# Main_mouse.net
KiCad netlist of a schematic drawn in EAGLE
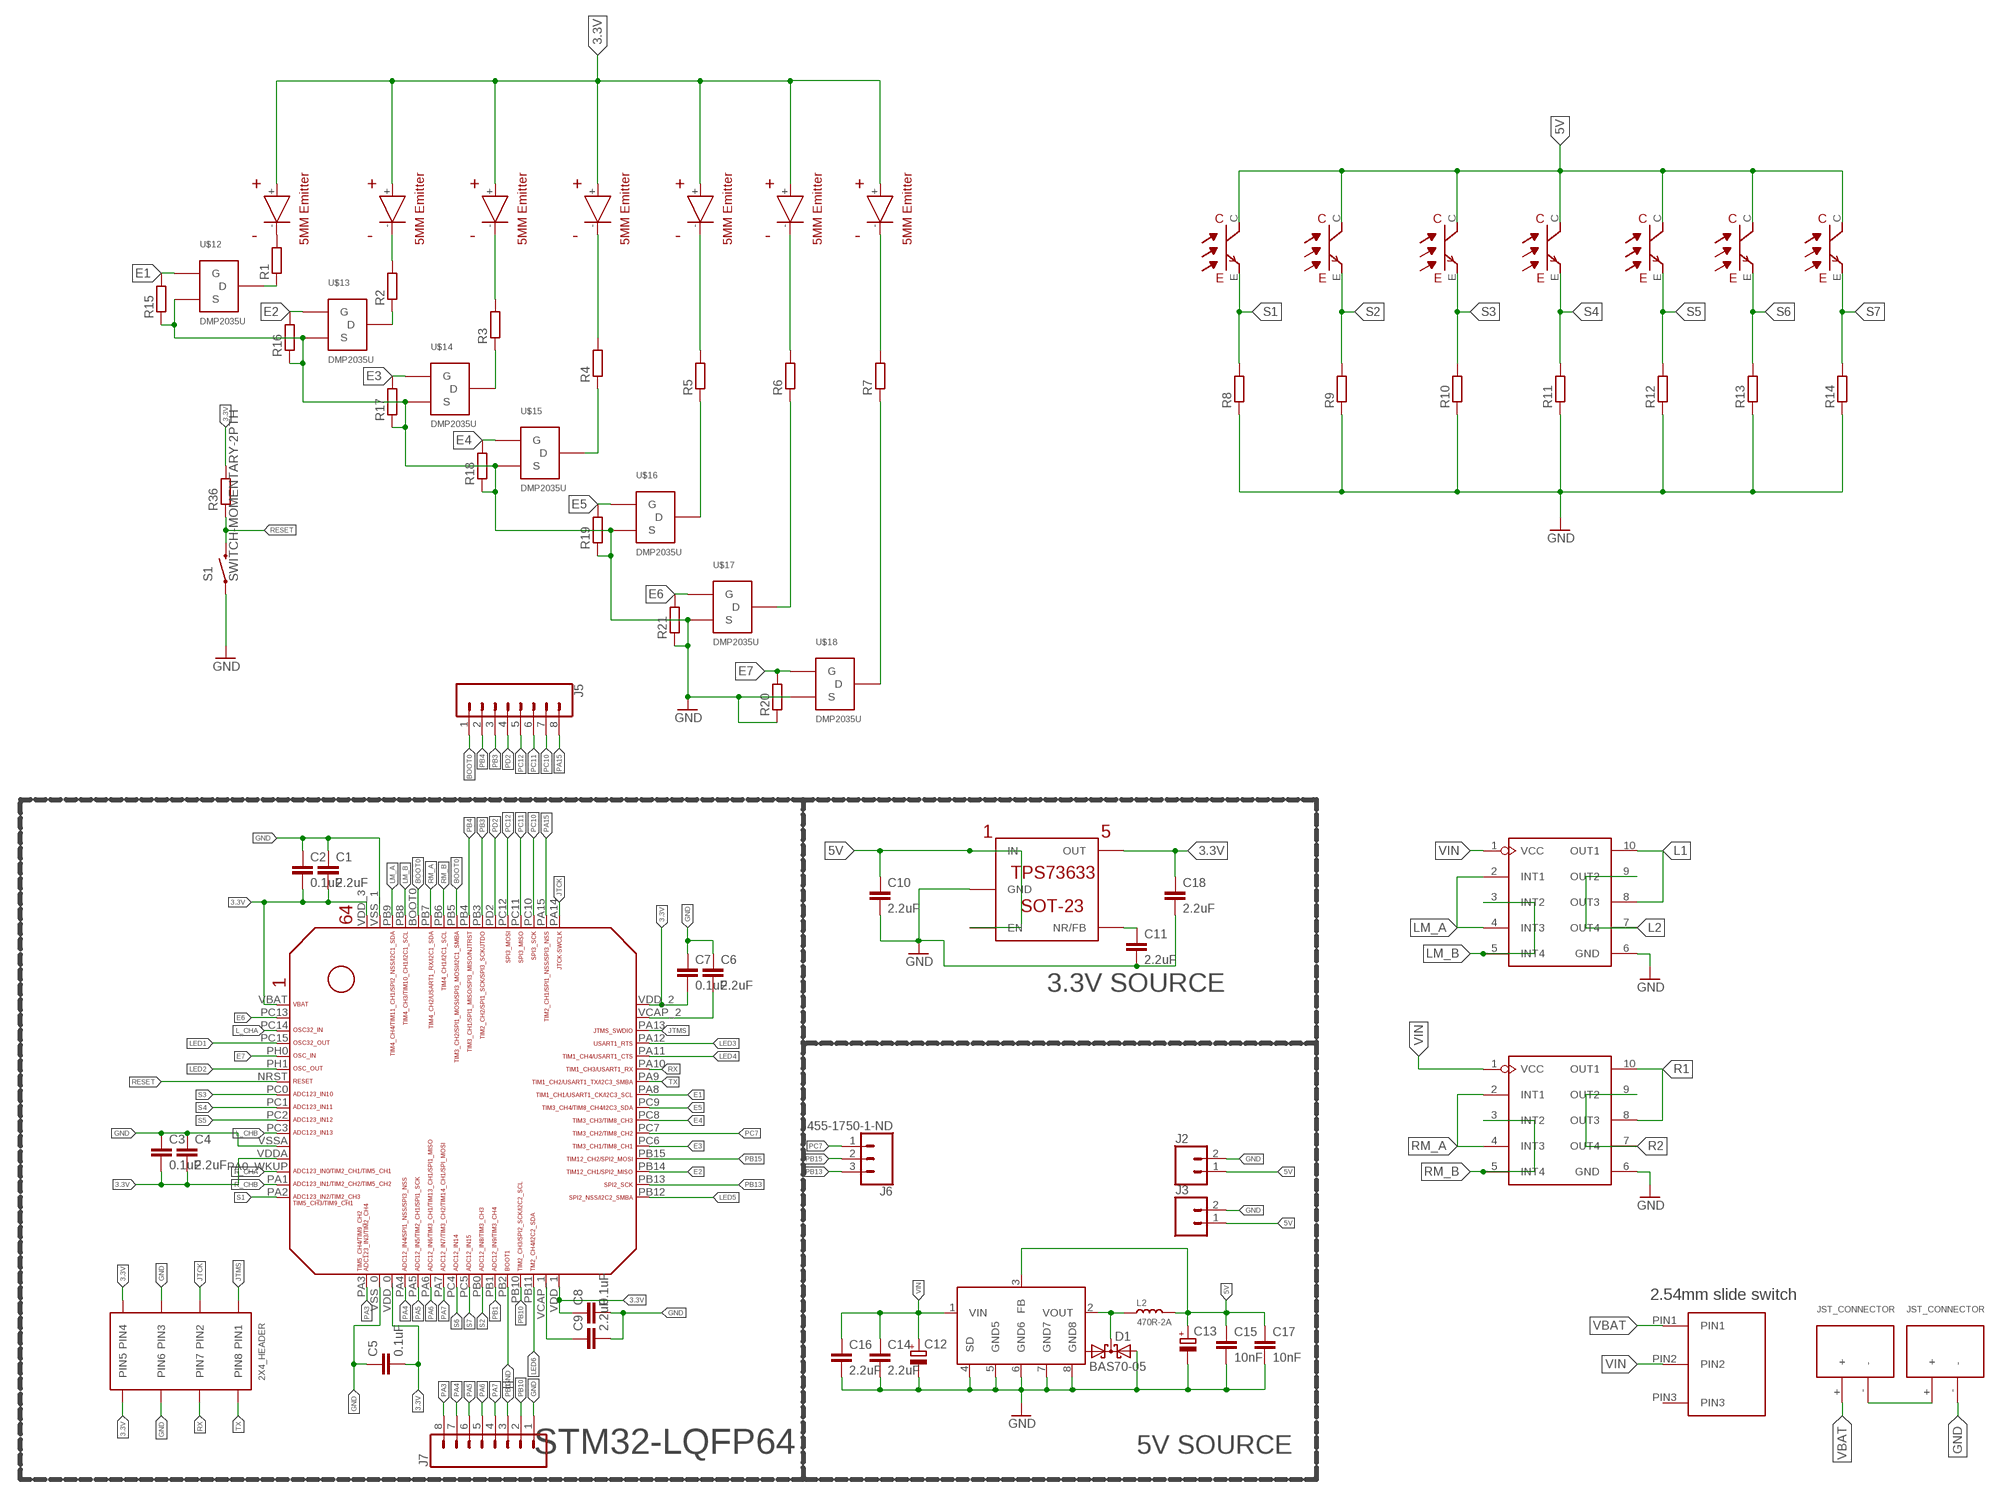
[diagram p0: schematic, sheet 1, part 1 of 2]
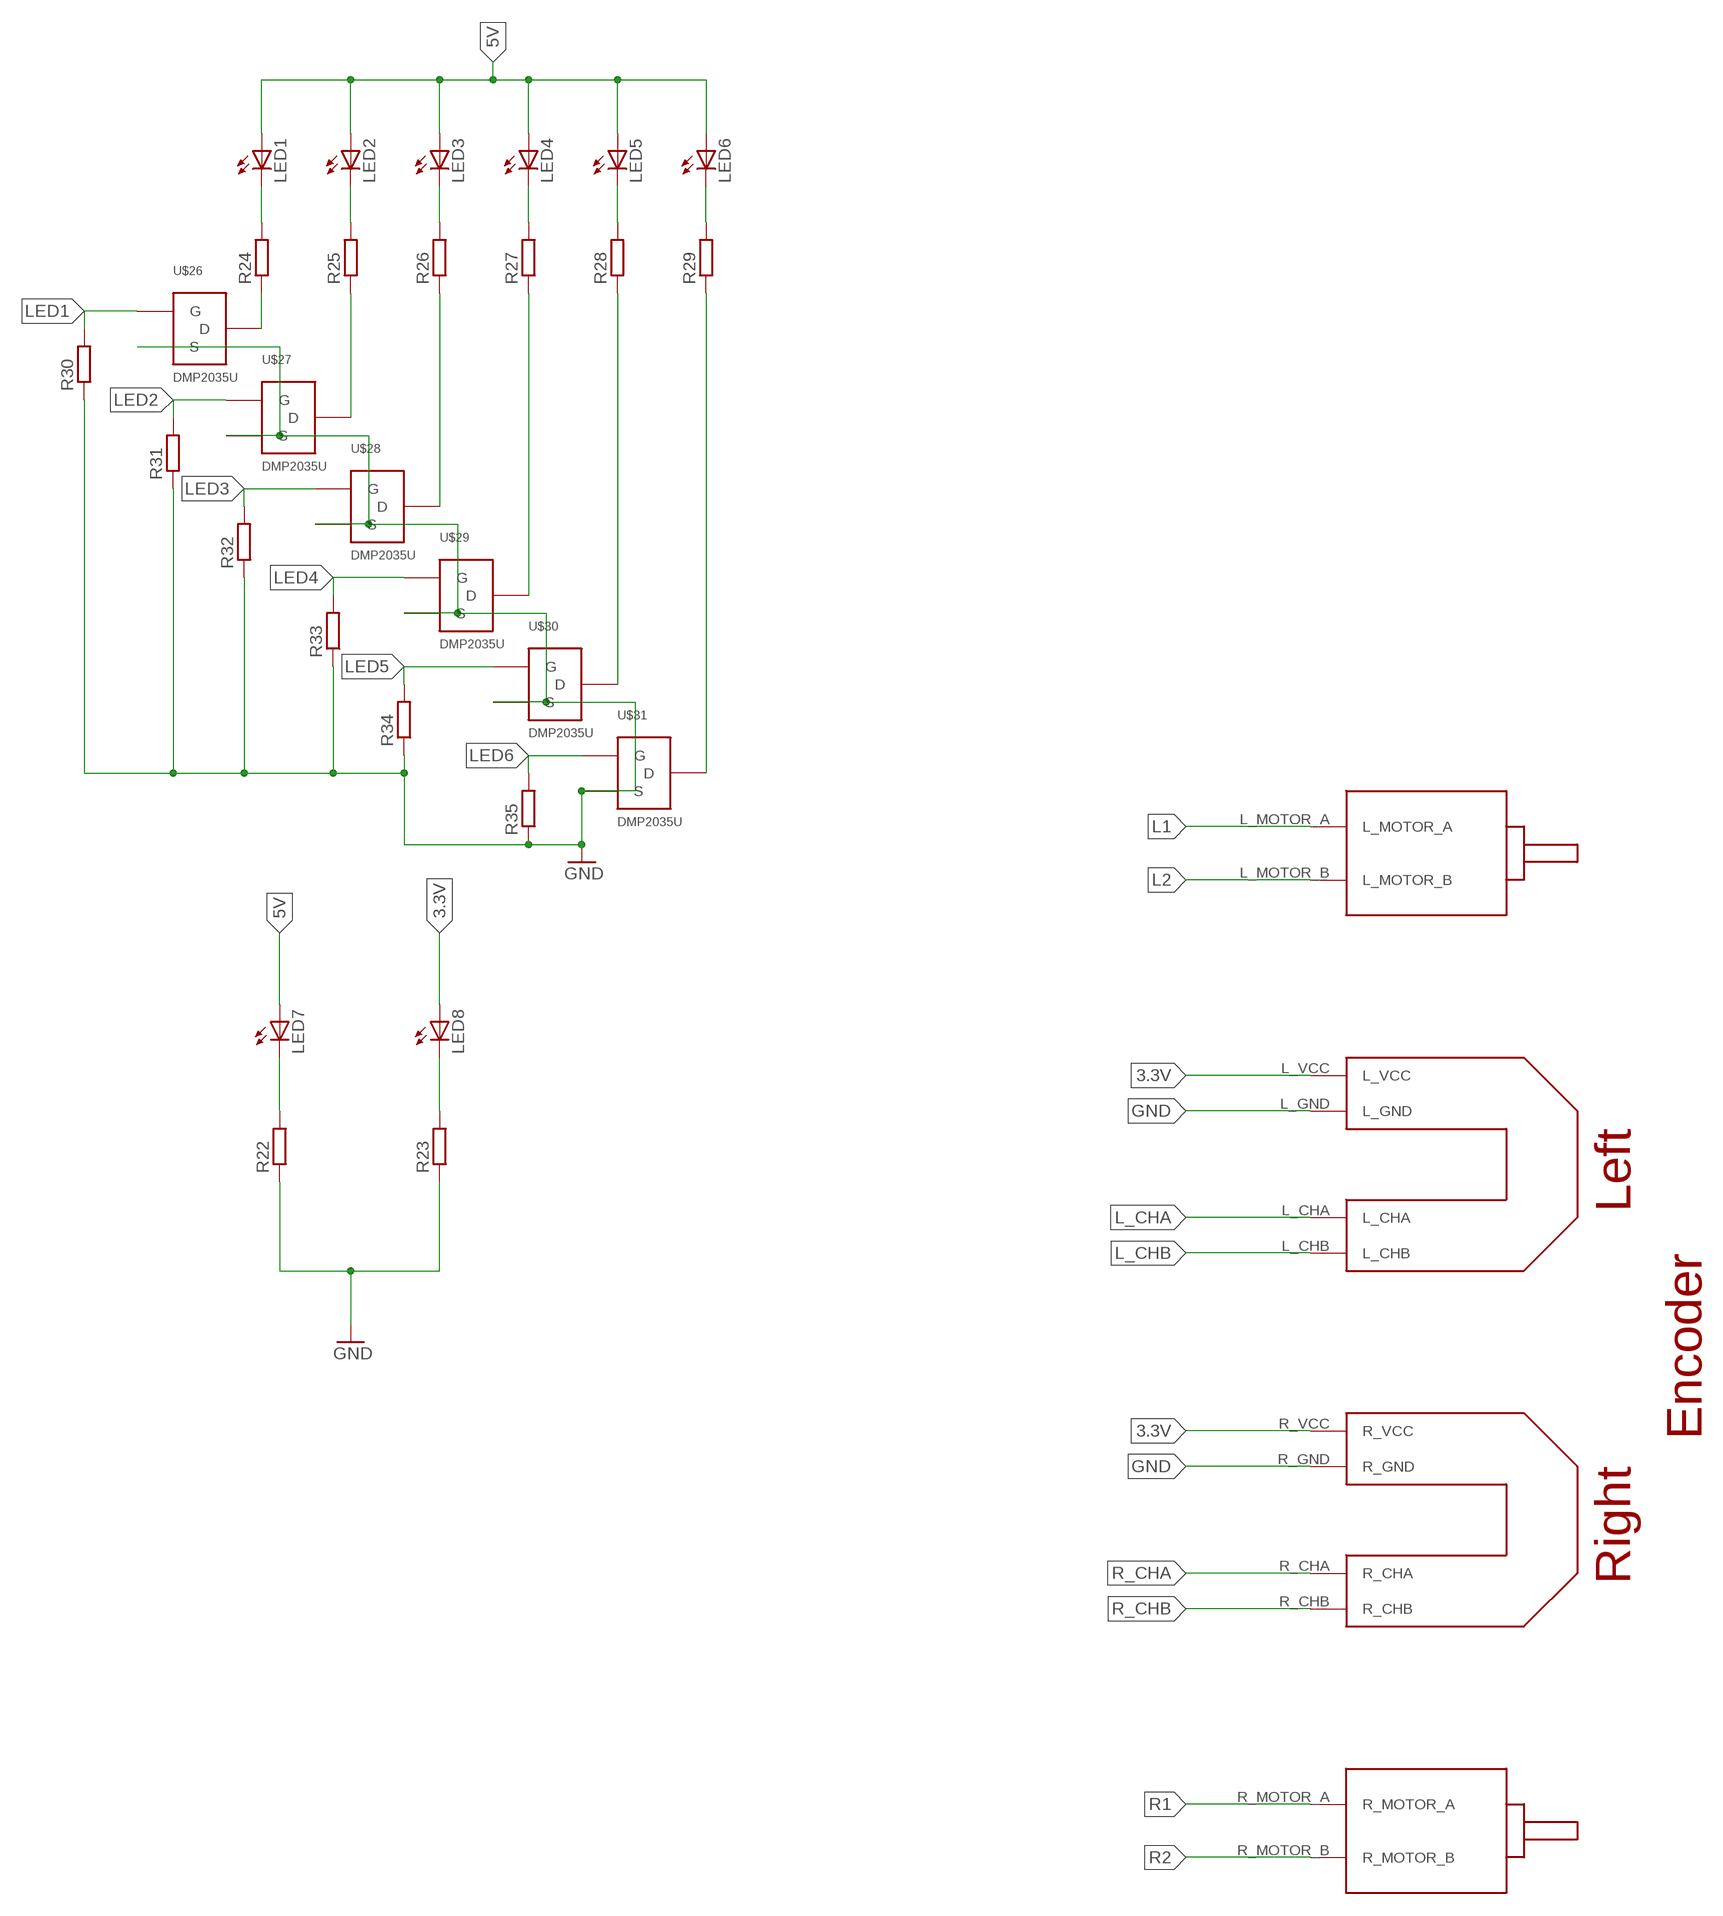
[diagram p1: schematic, sheet 1, part 2 of 2]

(export (version "E")
  (design (tool "Eeschema 10.0.6"))
  (components
    (comp (ref "C1")
      (value "2.2uF")
      (footprint "eagle-import:0603")
      (libsource (lib "eagle-import") (part "2.2UF-0603-10V-20%"))
    )
    (comp (ref "C2")
      (value "0.1uF")
      (footprint "eagle-import:0603")
      (libsource (lib "eagle-import") (part "0.1UF-0603-25V-(+80/-20%)"))
    )
    (comp (ref "C3")
      (value "0.1uF")
      (footprint "eagle-import:0603")
      (libsource (lib "eagle-import") (part "0.1UF-0603-25V-(+80/-20%)"))
    )
    (comp (ref "C4")
      (value "2.2uF")
      (footprint "eagle-import:0603")
      (libsource (lib "eagle-import") (part "2.2UF-0603-10V-20%"))
    )
    (comp (ref "C5")
      (value "0.1uF")
      (footprint "eagle-import:0603")
      (libsource (lib "eagle-import") (part "0.1UF-0603-25V-(+80/-20%)"))
    )
    (comp (ref "C6")
      (value "2.2uF")
      (footprint "eagle-import:0603")
      (libsource (lib "eagle-import") (part "2.2UF-0603-10V-20%"))
    )
    (comp (ref "C7")
      (value "0.1uF")
      (footprint "eagle-import:0603")
      (libsource (lib "eagle-import") (part "0.1UF-0603-25V-(+80/-20%)"))
    )
    (comp (ref "C8")
      (value "0.1uF")
      (footprint "eagle-import:0603")
      (libsource (lib "eagle-import") (part "0.1UF-0603-25V-(+80/-20%)"))
    )
    (comp (ref "C9")
      (value "2.2uF")
      (footprint "eagle-import:0603")
      (libsource (lib "eagle-import") (part "2.2UF-0603-10V-20%"))
    )
    (comp (ref "C10")
      (value "2.2uF")
      (footprint "eagle-import:0603")
      (libsource (lib "eagle-import") (part "2.2UF-0603-10V-20%"))
    )
    (comp (ref "C11")
      (value "2.2uF")
      (footprint "eagle-import:0603")
      (libsource (lib "eagle-import") (part "2.2UF-0603-10V-20%"))
    )
    (comp (ref "C12")
      (value "CPOL-EUSMCA")
      (footprint "eagle-import:SMC_A")
      (libsource (lib "eagle-import") (part "CPOL-EUSMCA"))
    )
    (comp (ref "C13")
      (value "CPOL-EUSMCC")
      (footprint "eagle-import:SMC_C")
      (libsource (lib "eagle-import") (part "CPOL-EUSMCC"))
    )
    (comp (ref "C14")
      (value "2.2uF")
      (footprint "eagle-import:0603")
      (libsource (lib "eagle-import") (part "2.2UF-0603-10V-20%"))
    )
    (comp (ref "C15")
      (value "10nF")
      (footprint "eagle-import:0603")
      (libsource (lib "eagle-import") (part "10NF-0603-50V-10%"))
    )
    (comp (ref "C16")
      (value "2.2uF")
      (footprint "eagle-import:0603")
      (libsource (lib "eagle-import") (part "2.2UF-0603-10V-20%"))
    )
    (comp (ref "C17")
      (value "10nF")
      (footprint "eagle-import:0603")
      (libsource (lib "eagle-import") (part "10NF-0603-50V-10%"))
    )
    (comp (ref "C18")
      (value "2.2uF")
      (footprint "eagle-import:0603")
      (libsource (lib "eagle-import") (part "2.2UF-0603-10V-20%"))
    )
    (comp (ref "D1")
      (value "BAS70-05")
      (footprint "eagle-import:SOT23")
      (libsource (lib "eagle-import") (part "BAS70-05"))
    )
    (comp (ref "J2")
      (value "CONN_02PTH3")
      (footprint "eagle-import:1X02_LONGPADS")
      (libsource (lib "eagle-import") (part "CONN_02PTH3"))
    )
    (comp (ref "J3")
      (value "CONN_02PTH3")
      (footprint "eagle-import:1X02_LONGPADS")
      (libsource (lib "eagle-import") (part "CONN_02PTH3"))
    )
    (comp (ref "J5")
      (value "CONN_08NO_SILK_FEMALE_PTH")
      (footprint "eagle-import:1X08_NO_SILK")
      (libsource (lib "eagle-import") (part "CONN_08NO_SILK_FEMALE_PTH"))
    )
    (comp (ref "J6")
      (value "455-1750-1-ND")
      (footprint "eagle-import:1X03")
      (libsource (lib "eagle-import") (part "CONN_03"))
    )
    (comp (ref "J7")
      (value "CONN_08NO_SILK_FEMALE_PTH")
      (footprint "eagle-import:1X08_NO_SILK")
      (libsource (lib "eagle-import") (part "CONN_08NO_SILK_FEMALE_PTH"))
    )
    (comp (ref "L2")
      (value "470R-2A")
      (footprint "eagle-import:L0805")
      (fields (field (name "MPN") "WLB2012-471T20"))
      (libsource (lib "eagle-import") (part "SMD-FERRITE-BEAD-470R-2A(0805)'0805'"))
    )
    (comp (ref "LED1")
      (value "LEDCHIP-LED0603")
      (footprint "eagle-import:CHIP-LED0603")
      (libsource (lib "eagle-import") (part "LEDCHIP-LED0603"))
    )
    (comp (ref "LED2")
      (value "LEDCHIP-LED0603")
      (footprint "eagle-import:CHIP-LED0603")
      (libsource (lib "eagle-import") (part "LEDCHIP-LED0603"))
    )
    (comp (ref "LED3")
      (value "LEDCHIP-LED0603")
      (footprint "eagle-import:CHIP-LED0603")
      (libsource (lib "eagle-import") (part "LEDCHIP-LED0603"))
    )
    (comp (ref "LED4")
      (value "LEDCHIP-LED0603")
      (footprint "eagle-import:CHIP-LED0603")
      (libsource (lib "eagle-import") (part "LEDCHIP-LED0603"))
    )
    (comp (ref "LED5")
      (value "LEDCHIP-LED0603")
      (footprint "eagle-import:CHIP-LED0603")
      (libsource (lib "eagle-import") (part "LEDCHIP-LED0603"))
    )
    (comp (ref "LED6")
      (value "LEDCHIP-LED0603")
      (footprint "eagle-import:CHIP-LED0603")
      (libsource (lib "eagle-import") (part "LEDCHIP-LED0603"))
    )
    (comp (ref "LED7")
      (value "LEDCHIP-LED0603")
      (footprint "eagle-import:CHIP-LED0603")
      (libsource (lib "eagle-import") (part "LEDCHIP-LED0603"))
    )
    (comp (ref "LED8")
      (value "LEDCHIP-LED0603")
      (footprint "eagle-import:CHIP-LED0603")
      (libsource (lib "eagle-import") (part "LEDCHIP-LED0603"))
    )
    (comp (ref "R1")
      (value "R-EU_R0603")
      (footprint "eagle-import:R0603")
      (libsource (lib "eagle-import") (part "R-EU_R0603"))
    )
    (comp (ref "R2")
      (value "R-EU_R0603")
      (footprint "eagle-import:R0603")
      (libsource (lib "eagle-import") (part "R-EU_R0603"))
    )
    (comp (ref "R3")
      (value "R-EU_R0603")
      (footprint "eagle-import:R0603")
      (libsource (lib "eagle-import") (part "R-EU_R0603"))
    )
    (comp (ref "R4")
      (value "R-EU_R0603")
      (footprint "eagle-import:R0603")
      (libsource (lib "eagle-import") (part "R-EU_R0603"))
    )
    (comp (ref "R5")
      (value "R-EU_R0603")
      (footprint "eagle-import:R0603")
      (libsource (lib "eagle-import") (part "R-EU_R0603"))
    )
    (comp (ref "R6")
      (value "R-EU_R0603")
      (footprint "eagle-import:R0603")
      (libsource (lib "eagle-import") (part "R-EU_R0603"))
    )
    (comp (ref "R7")
      (value "R-EU_R0603")
      (footprint "eagle-import:R0603")
      (libsource (lib "eagle-import") (part "R-EU_R0603"))
    )
    (comp (ref "R8")
      (value "R-EU_R0603")
      (footprint "eagle-import:R0603")
      (libsource (lib "eagle-import") (part "R-EU_R0603"))
    )
    (comp (ref "R9")
      (value "R-EU_R0603")
      (footprint "eagle-import:R0603")
      (libsource (lib "eagle-import") (part "R-EU_R0603"))
    )
    (comp (ref "R10")
      (value "R-EU_R0603")
      (footprint "eagle-import:R0603")
      (libsource (lib "eagle-import") (part "R-EU_R0603"))
    )
    (comp (ref "R11")
      (value "R-EU_R0603")
      (footprint "eagle-import:R0603")
      (libsource (lib "eagle-import") (part "R-EU_R0603"))
    )
    (comp (ref "R12")
      (value "R-EU_R0603")
      (footprint "eagle-import:R0603")
      (libsource (lib "eagle-import") (part "R-EU_R0603"))
    )
    (comp (ref "R13")
      (value "R-EU_R0603")
      (footprint "eagle-import:R0603")
      (libsource (lib "eagle-import") (part "R-EU_R0603"))
    )
    (comp (ref "R14")
      (value "R-EU_R0603")
      (footprint "eagle-import:R0603")
      (libsource (lib "eagle-import") (part "R-EU_R0603"))
    )
    (comp (ref "R15")
      (value "R-EU_R0603")
      (footprint "eagle-import:R0603")
      (libsource (lib "eagle-import") (part "R-EU_R0603"))
    )
    (comp (ref "R16")
      (value "R-EU_R0603")
      (footprint "eagle-import:R0603")
      (libsource (lib "eagle-import") (part "R-EU_R0603"))
    )
    (comp (ref "R17")
      (value "R-EU_R0603")
      (footprint "eagle-import:R0603")
      (libsource (lib "eagle-import") (part "R-EU_R0603"))
    )
    (comp (ref "R18")
      (value "R-EU_R0603")
      (footprint "eagle-import:R0603")
      (libsource (lib "eagle-import") (part "R-EU_R0603"))
    )
    (comp (ref "R19")
      (value "R-EU_R0603")
      (footprint "eagle-import:R0603")
      (libsource (lib "eagle-import") (part "R-EU_R0603"))
    )
    (comp (ref "R20")
      (value "R-EU_R0603")
      (footprint "eagle-import:R0603")
      (libsource (lib "eagle-import") (part "R-EU_R0603"))
    )
    (comp (ref "R21")
      (value "R-EU_R0603")
      (footprint "eagle-import:R0603")
      (libsource (lib "eagle-import") (part "R-EU_R0603"))
    )
    (comp (ref "R22")
      (value "R-EU_R0603")
      (footprint "eagle-import:R0603")
      (libsource (lib "eagle-import") (part "R-EU_R0603"))
    )
    (comp (ref "R23")
      (value "R-EU_R0603")
      (footprint "eagle-import:R0603")
      (libsource (lib "eagle-import") (part "R-EU_R0603"))
    )
    (comp (ref "R24")
      (value "R-EU_R0603")
      (footprint "eagle-import:R0603")
      (libsource (lib "eagle-import") (part "R-EU_R0603"))
    )
    (comp (ref "R25")
      (value "R-EU_R0603")
      (footprint "eagle-import:R0603")
      (libsource (lib "eagle-import") (part "R-EU_R0603"))
    )
    (comp (ref "R26")
      (value "R-EU_R0603")
      (footprint "eagle-import:R0603")
      (libsource (lib "eagle-import") (part "R-EU_R0603"))
    )
    (comp (ref "R27")
      (value "R-EU_R0603")
      (footprint "eagle-import:R0603")
      (libsource (lib "eagle-import") (part "R-EU_R0603"))
    )
    (comp (ref "R28")
      (value "R-EU_R0603")
      (footprint "eagle-import:R0603")
      (libsource (lib "eagle-import") (part "R-EU_R0603"))
    )
    (comp (ref "R29")
      (value "R-EU_R0603")
      (footprint "eagle-import:R0603")
      (libsource (lib "eagle-import") (part "R-EU_R0603"))
    )
    (comp (ref "R30")
      (value "R-EU_R0603")
      (footprint "eagle-import:R0603")
      (libsource (lib "eagle-import") (part "R-EU_R0603"))
    )
    (comp (ref "R31")
      (value "R-EU_R0603")
      (footprint "eagle-import:R0603")
      (libsource (lib "eagle-import") (part "R-EU_R0603"))
    )
    (comp (ref "R32")
      (value "R-EU_R0603")
      (footprint "eagle-import:R0603")
      (libsource (lib "eagle-import") (part "R-EU_R0603"))
    )
    (comp (ref "R33")
      (value "R-EU_R0603")
      (footprint "eagle-import:R0603")
      (libsource (lib "eagle-import") (part "R-EU_R0603"))
    )
    (comp (ref "R34")
      (value "R-EU_R0603")
      (footprint "eagle-import:R0603")
      (libsource (lib "eagle-import") (part "R-EU_R0603"))
    )
    (comp (ref "R35")
      (value "R-EU_R0603")
      (footprint "eagle-import:R0603")
      (libsource (lib "eagle-import") (part "R-EU_R0603"))
    )
    (comp (ref "R36")
      (value "R-EU_R0603")
      (footprint "eagle-import:R0603")
      (libsource (lib "eagle-import") (part "R-EU_R0603"))
    )
    (comp (ref "S1")
      (value "SWITCH-MOMENTARY-2PTH")
      (footprint "eagle-import:TACTILE-PTH")
      (libsource (lib "eagle-import") (part "SWITCH-MOMENTARY-2PTH"))
    )
    (comp (ref "U$1")
      (value "STM32F405/415_LQFP64")
      (footprint "eagle-import:STM32F405_415_LQFP64")
      (libsource (lib "eagle-import") (part "STM32F405/415_LQFP64"))
    )
    (comp (ref "U$2")
      (value "2X3_HEADER")
      (footprint "eagle-import:2X3_HEADER")
      (libsource (lib "eagle-import") (part "2X3_HEADER"))
    )
    (comp (ref "U$3")
      (value "AP1509-50SG-13")
      (footprint "eagle-import:SO08")
      (fields (field (name "MF") "Diodes Inc."))
      (libsource (lib "eagle-import") (part "AP1509-50SG-13"))
    )
    (comp (ref "U$4")
      (value "TPS73633(SOT-23)")
      (footprint "eagle-import:TPS73633(SOT-23)")
      (libsource (lib "eagle-import") (part "TPS73633(SOT-23)"))
    )
    (comp (ref "U$5")
      (value "EMITTER")
      (footprint "eagle-import:EMITTER")
      (libsource (lib "eagle-import") (part "EMITTER"))
    )
    (comp (ref "U$6")
      (value "EMITTER")
      (footprint "eagle-import:EMITTER")
      (libsource (lib "eagle-import") (part "EMITTER"))
    )
    (comp (ref "U$7")
      (value "EMITTER")
      (footprint "eagle-import:EMITTER")
      (libsource (lib "eagle-import") (part "EMITTER"))
    )
    (comp (ref "U$8")
      (value "EMITTER")
      (footprint "eagle-import:EMITTER")
      (libsource (lib "eagle-import") (part "EMITTER"))
    )
    (comp (ref "U$9")
      (value "EMITTER")
      (footprint "eagle-import:EMITTER")
      (libsource (lib "eagle-import") (part "EMITTER"))
    )
    (comp (ref "U$10")
      (value "EMITTER")
      (footprint "eagle-import:EMITTER")
      (libsource (lib "eagle-import") (part "EMITTER"))
    )
    (comp (ref "U$11")
      (value "EMITTER")
      (footprint "eagle-import:EMITTER")
      (libsource (lib "eagle-import") (part "EMITTER"))
    )
    (comp (ref "U$12")
      (value "DMP2035U")
      (footprint "eagle-import:SOT23")
      (fields (field (name "MF") "Diodes Inc."))
      (libsource (lib "eagle-import") (part "DMP2035U"))
    )
    (comp (ref "U$13")
      (value "DMP2035U")
      (footprint "eagle-import:SOT23")
      (fields (field (name "MF") "Diodes Inc."))
      (libsource (lib "eagle-import") (part "DMP2035U"))
    )
    (comp (ref "U$14")
      (value "DMP2035U")
      (footprint "eagle-import:SOT23")
      (fields (field (name "MF") "Diodes Inc."))
      (libsource (lib "eagle-import") (part "DMP2035U"))
    )
    (comp (ref "U$15")
      (value "DMP2035U")
      (footprint "eagle-import:SOT23")
      (fields (field (name "MF") "Diodes Inc."))
      (libsource (lib "eagle-import") (part "DMP2035U"))
    )
    (comp (ref "U$16")
      (value "DMP2035U")
      (footprint "eagle-import:SOT23")
      (fields (field (name "MF") "Diodes Inc."))
      (libsource (lib "eagle-import") (part "DMP2035U"))
    )
    (comp (ref "U$17")
      (value "DMP2035U")
      (footprint "eagle-import:SOT23")
      (fields (field (name "MF") "Diodes Inc."))
      (libsource (lib "eagle-import") (part "DMP2035U"))
    )
    (comp (ref "U$18")
      (value "DMP2035U")
      (footprint "eagle-import:SOT23")
      (fields (field (name "MF") "Diodes Inc."))
      (libsource (lib "eagle-import") (part "DMP2035U"))
    )
    (comp (ref "U$19")
      (value "RECEIVER")
      (footprint "eagle-import:RECEIVER")
      (libsource (lib "eagle-import") (part "RECEIVER"))
    )
    (comp (ref "U$20")
      (value "RECEIVER")
      (footprint "eagle-import:RECEIVER")
      (libsource (lib "eagle-import") (part "RECEIVER"))
    )
    (comp (ref "U$21")
      (value "RECEIVER")
      (footprint "eagle-import:RECEIVER")
      (libsource (lib "eagle-import") (part "RECEIVER"))
    )
    (comp (ref "U$22")
      (value "RECEIVER")
      (footprint "eagle-import:RECEIVER")
      (libsource (lib "eagle-import") (part "RECEIVER"))
    )
    (comp (ref "U$23")
      (value "RECEIVER")
      (footprint "eagle-import:RECEIVER")
      (libsource (lib "eagle-import") (part "RECEIVER"))
    )
    (comp (ref "U$24")
      (value "RECEIVER")
      (footprint "eagle-import:RECEIVER")
      (libsource (lib "eagle-import") (part "RECEIVER"))
    )
    (comp (ref "U$25")
      (value "RECEIVER")
      (footprint "eagle-import:RECEIVER")
      (libsource (lib "eagle-import") (part "RECEIVER"))
    )
    (comp (ref "U$26")
      (value "DMP2035U")
      (footprint "eagle-import:SOT23")
      (fields (field (name "MF") "Diodes Inc."))
      (libsource (lib "eagle-import") (part "DMP2035U"))
    )
    (comp (ref "U$27")
      (value "DMP2035U")
      (footprint "eagle-import:SOT23")
      (fields (field (name "MF") "Diodes Inc."))
      (libsource (lib "eagle-import") (part "DMP2035U"))
    )
    (comp (ref "U$28")
      (value "DMP2035U")
      (footprint "eagle-import:SOT23")
      (fields (field (name "MF") "Diodes Inc."))
      (libsource (lib "eagle-import") (part "DMP2035U"))
    )
    (comp (ref "U$29")
      (value "DMP2035U")
      (footprint "eagle-import:SOT23")
      (fields (field (name "MF") "Diodes Inc."))
      (libsource (lib "eagle-import") (part "DMP2035U"))
    )
    (comp (ref "U$30")
      (value "DMP2035U")
      (footprint "eagle-import:SOT23")
      (fields (field (name "MF") "Diodes Inc."))
      (libsource (lib "eagle-import") (part "DMP2035U"))
    )
    (comp (ref "U$31")
      (value "DMP2035U")
      (footprint "eagle-import:SOT23")
      (fields (field (name "MF") "Diodes Inc."))
      (libsource (lib "eagle-import") (part "DMP2035U"))
    )
    (comp (ref "U$32")
      (value "TS02_SWITCH")
      (footprint "eagle-import:TS02_SWITCH")
      (libsource (lib "eagle-import") (part "TS02_SWITCH"))
    )
    (comp (ref "U$33")
      (value "JST_CONNECTOR_FEMALE")
      (footprint "eagle-import:JST_CONNECTOR_FEMALE")
      (libsource (lib "eagle-import") (part "JST_CONNECTOR_FEMALE"))
    )
    (comp (ref "U$34")
      (value "JST_CONNECTOR_FEMALE")
      (footprint "eagle-import:JST_CONNECTOR_FEMALE")
      (libsource (lib "eagle-import") (part "JST_CONNECTOR_FEMALE"))
    )
    (comp (ref "U$35")
      (value "FUTURA_V1.0_MOTOR_MOUNT")
      (footprint "eagle-import:FUTURA_V1.0_MOTOT_MOUNT")
      (libsource (lib "eagle-import") (part "FUTURA_V1.0_MOTOR_MOUNT"))
    )
    (comp (ref "U1")
      (value "DRIVER-LV8548MC-AH(SOIC10)")
      (footprint "eagle-import:SOIC10-1.0-5X4MM")
      (fields (field (name "MF") "ON Semiconductor") (field (name "MP") "LV8548MC-AH"))
      (libsource (lib "eagle-import") (part "DRIVER-LV8548MC-AH(SOIC10)"))
    )
    (comp (ref "U2")
      (value "DRIVER-LV8548MC-AH(SOIC10)")
      (footprint "eagle-import:SOIC10-1.0-5X4MM")
      (fields (field (name "MF") "ON Semiconductor") (field (name "MP") "LV8548MC-AH"))
      (libsource (lib "eagle-import") (part "DRIVER-LV8548MC-AH(SOIC10)"))
    )
  )
  (nets
    (net (code "1") (name "3.3V") (class "Default")
      (node (ref "C1") (pin "2") (pinfunction "2_2") (pintype "passive"))
      (node (ref "C18") (pin "1") (pinfunction "1_1") (pintype "passive"))
      (node (ref "C2") (pin "2") (pinfunction "2_2") (pintype "passive"))
      (node (ref "C3") (pin "2") (pinfunction "2_2") (pintype "passive"))
      (node (ref "C4") (pin "2") (pinfunction "2_2") (pintype "passive"))
      (node (ref "C5") (pin "2") (pinfunction "2_2") (pintype "passive"))
      (node (ref "C7") (pin "2") (pinfunction "2_2") (pintype "passive"))
      (node (ref "C8") (pin "1") (pinfunction "1_1") (pintype "passive"))
      (node (ref "LED8") (pin "A") (pinfunction "A_A") (pintype "passive"))
      (node (ref "R36") (pin "2") (pinfunction "2_2") (pintype "passive"))
      (node (ref "U$1") (pin "VBAT") (pinfunction "VBAT_VBAT") (pintype "bidirectional"))
      (node (ref "U$1") (pin "VDDA") (pinfunction "VDDA_VDDA") (pintype "bidirectional"))
      (node (ref "U$1") (pin "VDD_0") (pinfunction "VDD_0_VDD_0") (pintype "bidirectional"))
      (node (ref "U$1") (pin "VDD_1") (pinfunction "VDD_1_VDD_1") (pintype "bidirectional"))
      (node (ref "U$1") (pin "VDD_2") (pinfunction "VDD_2_VDD_2") (pintype "bidirectional"))
      (node (ref "U$1") (pin "VDD_3") (pinfunction "VDD_3_VDD_3") (pintype "bidirectional"))
      (node (ref "U$10") (pin "+") (pinfunction "+_+") (pintype "bidirectional"))
      (node (ref "U$11") (pin "+") (pinfunction "+_+") (pintype "bidirectional"))
      (node (ref "U$2") (pin "PIN4") (pinfunction "PIN4_PIN4") (pintype "bidirectional"))
      (node (ref "U$2") (pin "PIN5") (pinfunction "PIN5_PIN5") (pintype "bidirectional"))
      (node (ref "U$35") (pin "L_VCC") (pinfunction "L_VCC_L_VCC") (pintype "bidirectional"))
      (node (ref "U$35") (pin "R_VCC") (pinfunction "R_VCC_R_VCC") (pintype "bidirectional"))
      (node (ref "U$4") (pin "OUT") (pinfunction "OUT_OUT") (pintype "bidirectional"))
      (node (ref "U$5") (pin "+") (pinfunction "+_+") (pintype "bidirectional"))
      (node (ref "U$6") (pin "+") (pinfunction "+_+") (pintype "bidirectional"))
      (node (ref "U$7") (pin "+") (pinfunction "+_+") (pintype "bidirectional"))
      (node (ref "U$8") (pin "+") (pinfunction "+_+") (pintype "bidirectional"))
      (node (ref "U$9") (pin "+") (pinfunction "+_+") (pintype "bidirectional"))
    )
    (net (code "2") (name "5V") (class "Default")
      (node (ref "C10") (pin "1") (pinfunction "1_1") (pintype "passive"))
      (node (ref "C13") (pin "+") (pinfunction "+_+") (pintype "passive"))
      (node (ref "C15") (pin "1") (pinfunction "1_1") (pintype "passive"))
      (node (ref "C17") (pin "1") (pinfunction "1_1") (pintype "passive"))
      (node (ref "J2") (pin "1") (pinfunction "1_1") (pintype "passive"))
      (node (ref "J3") (pin "1") (pinfunction "1_1") (pintype "passive"))
      (node (ref "L2") (pin "2") (pinfunction "2_2") (pintype "passive"))
      (node (ref "LED1") (pin "A") (pinfunction "A_A") (pintype "passive"))
      (node (ref "LED2") (pin "A") (pinfunction "A_A") (pintype "passive"))
      (node (ref "LED3") (pin "A") (pinfunction "A_A") (pintype "passive"))
      (node (ref "LED4") (pin "A") (pinfunction "A_A") (pintype "passive"))
      (node (ref "LED5") (pin "A") (pinfunction "A_A") (pintype "passive"))
      (node (ref "LED6") (pin "A") (pinfunction "A_A") (pintype "passive"))
      (node (ref "LED7") (pin "A") (pinfunction "A_A") (pintype "passive"))
      (node (ref "U$19") (pin "C") (pinfunction "C_C") (pintype "bidirectional"))
      (node (ref "U$20") (pin "C") (pinfunction "C_C") (pintype "bidirectional"))
      (node (ref "U$21") (pin "C") (pinfunction "C_C") (pintype "bidirectional"))
      (node (ref "U$22") (pin "C") (pinfunction "C_C") (pintype "bidirectional"))
      (node (ref "U$23") (pin "C") (pinfunction "C_C") (pintype "bidirectional"))
      (node (ref "U$24") (pin "C") (pinfunction "C_C") (pintype "bidirectional"))
      (node (ref "U$25") (pin "C") (pinfunction "C_C") (pintype "bidirectional"))
      (node (ref "U$3") (pin "3") (pinfunction "FB_3") (pintype "bidirectional"))
      (node (ref "U$4") (pin "EN") (pinfunction "EN_EN") (pintype "bidirectional"))
      (node (ref "U$4") (pin "IN") (pinfunction "IN_IN") (pintype "bidirectional"))
    )
    (net (code "3") (name "BOOT0") (class "Default")
      (node (ref "J5") (pin "1") (pinfunction "1_1") (pintype "passive"))
      (node (ref "U$1") (pin "BOOT0") (pinfunction "BOOT0_BOOT0") (pintype "bidirectional"))
      (node (ref "U$1") (pin "PB5") (pinfunction "PB5_PB5") (pintype "bidirectional"))
    )
    (net (code "4") (name "E1") (class "Default")
      (node (ref "R15") (pin "2") (pinfunction "2_2") (pintype "passive"))
      (node (ref "U$1") (pin "PA8") (pinfunction "PA8_PA8") (pintype "bidirectional"))
      (node (ref "U$12") (pin "1") (pinfunction "G_1") (pintype "bidirectional"))
    )
    (net (code "5") (name "E2") (class "Default")
      (node (ref "R16") (pin "2") (pinfunction "2_2") (pintype "passive"))
      (node (ref "U$1") (pin "PB14") (pinfunction "PB14_PB14") (pintype "bidirectional"))
      (node (ref "U$13") (pin "1") (pinfunction "G_1") (pintype "bidirectional"))
    )
    (net (code "6") (name "E3") (class "Default")
      (node (ref "R17") (pin "2") (pinfunction "2_2") (pintype "passive"))
      (node (ref "U$1") (pin "PC6") (pinfunction "PC6_PC6") (pintype "bidirectional"))
      (node (ref "U$14") (pin "1") (pinfunction "G_1") (pintype "bidirectional"))
    )
    (net (code "7") (name "E4") (class "Default")
      (node (ref "R18") (pin "2") (pinfunction "2_2") (pintype "passive"))
      (node (ref "U$1") (pin "PC8") (pinfunction "PC8_PC8") (pintype "bidirectional"))
      (node (ref "U$15") (pin "1") (pinfunction "G_1") (pintype "bidirectional"))
    )
    (net (code "8") (name "E5") (class "Default")
      (node (ref "R19") (pin "2") (pinfunction "2_2") (pintype "passive"))
      (node (ref "U$1") (pin "PC9") (pinfunction "PC9_PC9") (pintype "bidirectional"))
      (node (ref "U$16") (pin "1") (pinfunction "G_1") (pintype "bidirectional"))
    )
    (net (code "9") (name "E6") (class "Default")
      (node (ref "R21") (pin "2") (pinfunction "2_2") (pintype "passive"))
      (node (ref "U$1") (pin "PC13") (pinfunction "PC13_PC13") (pintype "bidirectional"))
      (node (ref "U$17") (pin "1") (pinfunction "G_1") (pintype "bidirectional"))
    )
    (net (code "10") (name "E7") (class "Default")
      (node (ref "R20") (pin "2") (pinfunction "2_2") (pintype "passive"))
      (node (ref "U$1") (pin "PH0") (pinfunction "PH0_PH0") (pintype "bidirectional"))
      (node (ref "U$18") (pin "1") (pinfunction "G_1") (pintype "bidirectional"))
    )
    (net (code "11") (name "GND") (class "Default")
      (node (ref "C1") (pin "1") (pinfunction "1_1") (pintype "passive"))
      (node (ref "C10") (pin "2") (pinfunction "2_2") (pintype "passive"))
      (node (ref "C11") (pin "2") (pinfunction "2_2") (pintype "passive"))
      (node (ref "C12") (pin "-") (pinfunction "-_-") (pintype "passive"))
      (node (ref "C13") (pin "-") (pinfunction "-_-") (pintype "passive"))
      (node (ref "C14") (pin "2") (pinfunction "2_2") (pintype "passive"))
      (node (ref "C15") (pin "2") (pinfunction "2_2") (pintype "passive"))
      (node (ref "C16") (pin "2") (pinfunction "2_2") (pintype "passive"))
      (node (ref "C17") (pin "2") (pinfunction "2_2") (pintype "passive"))
      (node (ref "C18") (pin "2") (pinfunction "2_2") (pintype "passive"))
      (node (ref "C2") (pin "1") (pinfunction "1_1") (pintype "passive"))
      (node (ref "C3") (pin "1") (pinfunction "1_1") (pintype "passive"))
      (node (ref "C4") (pin "1") (pinfunction "1_1") (pintype "passive"))
      (node (ref "C5") (pin "1") (pinfunction "1_1") (pintype "passive"))
      (node (ref "C6") (pin "1") (pinfunction "1_1") (pintype "passive"))
      (node (ref "C7") (pin "1") (pinfunction "1_1") (pintype "passive"))
      (node (ref "C8") (pin "2") (pinfunction "2_2") (pintype "passive"))
      (node (ref "C9") (pin "2") (pinfunction "2_2") (pintype "passive"))
      (node (ref "D1") (pin "2") (pinfunction "A2_2") (pintype "passive"))
      (node (ref "J2") (pin "2") (pinfunction "2_2") (pintype "passive"))
      (node (ref "J3") (pin "2") (pinfunction "2_2") (pintype "passive"))
      (node (ref "J7") (pin "1") (pinfunction "1_1") (pintype "passive"))
      (node (ref "R10") (pin "1") (pinfunction "1_1") (pintype "passive"))
      (node (ref "R11") (pin "1") (pinfunction "1_1") (pintype "passive"))
      (node (ref "R12") (pin "1") (pinfunction "1_1") (pintype "passive"))
      (node (ref "R13") (pin "1") (pinfunction "1_1") (pintype "passive"))
      (node (ref "R14") (pin "1") (pinfunction "1_1") (pintype "passive"))
      (node (ref "R15") (pin "1") (pinfunction "1_1") (pintype "passive"))
      (node (ref "R16") (pin "1") (pinfunction "1_1") (pintype "passive"))
      (node (ref "R17") (pin "1") (pinfunction "1_1") (pintype "passive"))
      (node (ref "R18") (pin "1") (pinfunction "1_1") (pintype "passive"))
      (node (ref "R19") (pin "1") (pinfunction "1_1") (pintype "passive"))
      (node (ref "R20") (pin "1") (pinfunction "1_1") (pintype "passive"))
      (node (ref "R21") (pin "1") (pinfunction "1_1") (pintype "passive"))
      (node (ref "R22") (pin "1") (pinfunction "1_1") (pintype "passive"))
      (node (ref "R23") (pin "1") (pinfunction "1_1") (pintype "passive"))
      (node (ref "R30") (pin "1") (pinfunction "1_1") (pintype "passive"))
      (node (ref "R31") (pin "1") (pinfunction "1_1") (pintype "passive"))
      (node (ref "R32") (pin "1") (pinfunction "1_1") (pintype "passive"))
      (node (ref "R33") (pin "1") (pinfunction "1_1") (pintype "passive"))
      (node (ref "R34") (pin "1") (pinfunction "1_1") (pintype "passive"))
      (node (ref "R35") (pin "1") (pinfunction "1_1") (pintype "passive"))
      (node (ref "R8") (pin "1") (pinfunction "1_1") (pintype "passive"))
      (node (ref "R9") (pin "1") (pinfunction "1_1") (pintype "passive"))
      (node (ref "S1") (pin "1") (pinfunction "1_1") (pintype "passive"))
      (node (ref "U$1") (pin "PB2") (pinfunction "PB2_PB2") (pintype "bidirectional"))
      (node (ref "U$1") (pin "VSSA") (pinfunction "VSSA_VSSA") (pintype "bidirectional"))
      (node (ref "U$1") (pin "VSS_0") (pinfunction "VSS_0_VSS_0") (pintype "bidirectional"))
      (node (ref "U$1") (pin "VSS_1") (pinfunction "VSS_1_VSS_1") (pintype "bidirectional"))
      (node (ref "U$12") (pin "2") (pinfunction "S_2") (pintype "bidirectional"))
      (node (ref "U$13") (pin "2") (pinfunction "S_2") (pintype "bidirectional"))
      (node (ref "U$14") (pin "2") (pinfunction "S_2") (pintype "bidirectional"))
      (node (ref "U$15") (pin "2") (pinfunction "S_2") (pintype "bidirectional"))
      (node (ref "U$16") (pin "2") (pinfunction "S_2") (pintype "bidirectional"))
      (node (ref "U$17") (pin "2") (pinfunction "S_2") (pintype "bidirectional"))
      (node (ref "U$18") (pin "2") (pinfunction "S_2") (pintype "bidirectional"))
      (node (ref "U$2") (pin "PIN3") (pinfunction "PIN3_PIN3") (pintype "bidirectional"))
      (node (ref "U$2") (pin "PIN6") (pinfunction "PIN6_PIN6") (pintype "bidirectional"))
      (node (ref "U$26") (pin "2") (pinfunction "S_2") (pintype "bidirectional"))
      (node (ref "U$27") (pin "2") (pinfunction "S_2") (pintype "bidirectional"))
      (node (ref "U$28") (pin "2") (pinfunction "S_2") (pintype "bidirectional"))
      (node (ref "U$29") (pin "2") (pinfunction "S_2") (pintype "bidirectional"))
      (node (ref "U$3") (pin "4") (pinfunction "SD_4") (pintype "bidirectional"))
      (node (ref "U$3") (pin "5") (pinfunction "GND5_5") (pintype "bidirectional"))
      (node (ref "U$3") (pin "6") (pinfunction "GND6_6") (pintype "bidirectional"))
      (node (ref "U$3") (pin "7") (pinfunction "GND7_7") (pintype "bidirectional"))
      (node (ref "U$3") (pin "8") (pinfunction "GND8_8") (pintype "bidirectional"))
      (node (ref "U$30") (pin "2") (pinfunction "S_2") (pintype "bidirectional"))
      (node (ref "U$31") (pin "2") (pinfunction "S_2") (pintype "bidirectional"))
      (node (ref "U$34") (pin "-") (pinfunction "-_-") (pintype "bidirectional"))
      (node (ref "U$35") (pin "L_GND") (pinfunction "L_GND_L_GND") (pintype "bidirectional"))
      (node (ref "U$35") (pin "R_GND") (pinfunction "R_GND_R_GND") (pintype "bidirectional"))
      (node (ref "U$4") (pin "GND") (pinfunction "GND_GND") (pintype "bidirectional"))
      (node (ref "U1") (pin "6") (pinfunction "GND_6") (pintype "bidirectional"))
      (node (ref "U2") (pin "6") (pinfunction "GND_6") (pintype "bidirectional"))
    )
    (net (code "12") (name "JTCK") (class "Default")
      (node (ref "U$1") (pin "PA14") (pinfunction "PA14_PA14") (pintype "bidirectional"))
      (node (ref "U$2") (pin "PIN2") (pinfunction "PIN2_PIN2") (pintype "bidirectional"))
    )
    (net (code "13") (name "JTMS") (class "Default")
      (node (ref "U$1") (pin "PA13") (pinfunction "PA13_PA13") (pintype "bidirectional"))
      (node (ref "U$2") (pin "PIN1") (pinfunction "PIN1_PIN1") (pintype "bidirectional"))
    )
    (net (code "14") (name "L1") (class "Default")
      (node (ref "U$35") (pin "L_MOTOR_A") (pinfunction "L_MOTOR_A_L_MOTOR_A") (pintype "bidirectional"))
      (node (ref "U1") (pin "10") (pinfunction "OUT1_10") (pintype "bidirectional"))
      (node (ref "U1") (pin "8") (pinfunction "OUT3_8") (pintype "bidirectional"))
    )
    (net (code "15") (name "L2") (class "Default")
      (node (ref "U$35") (pin "L_MOTOR_B") (pinfunction "L_MOTOR_B_L_MOTOR_B") (pintype "bidirectional"))
      (node (ref "U1") (pin "7") (pinfunction "OUT4_7") (pintype "bidirectional"))
      (node (ref "U1") (pin "9") (pinfunction "OUT2_9") (pintype "bidirectional"))
    )
    (net (code "16") (name "LED1") (class "Default")
      (node (ref "R30") (pin "2") (pinfunction "2_2") (pintype "passive"))
      (node (ref "U$1") (pin "PC15") (pinfunction "PC15_PC15") (pintype "bidirectional"))
      (node (ref "U$26") (pin "1") (pinfunction "G_1") (pintype "bidirectional"))
    )
    (net (code "17") (name "LED2") (class "Default")
      (node (ref "R31") (pin "2") (pinfunction "2_2") (pintype "passive"))
      (node (ref "U$1") (pin "PH1") (pinfunction "PH1_PH1") (pintype "bidirectional"))
      (node (ref "U$27") (pin "1") (pinfunction "G_1") (pintype "bidirectional"))
    )
    (net (code "18") (name "LED3") (class "Default")
      (node (ref "R32") (pin "2") (pinfunction "2_2") (pintype "passive"))
      (node (ref "U$1") (pin "PA12") (pinfunction "PA12_PA12") (pintype "bidirectional"))
      (node (ref "U$28") (pin "1") (pinfunction "G_1") (pintype "bidirectional"))
    )
    (net (code "19") (name "LED4") (class "Default")
      (node (ref "R33") (pin "2") (pinfunction "2_2") (pintype "passive"))
      (node (ref "U$1") (pin "PA11") (pinfunction "PA11_PA11") (pintype "bidirectional"))
      (node (ref "U$29") (pin "1") (pinfunction "G_1") (pintype "bidirectional"))
    )
    (net (code "20") (name "LED5") (class "Default")
      (node (ref "R34") (pin "2") (pinfunction "2_2") (pintype "passive"))
      (node (ref "U$1") (pin "PB12") (pinfunction "PB12_PB12") (pintype "bidirectional"))
      (node (ref "U$30") (pin "1") (pinfunction "G_1") (pintype "bidirectional"))
    )
    (net (code "21") (name "LED6") (class "Default")
      (node (ref "R35") (pin "2") (pinfunction "2_2") (pintype "passive"))
      (node (ref "U$1") (pin "PB11") (pinfunction "PB11_PB11") (pintype "bidirectional"))
      (node (ref "U$31") (pin "1") (pinfunction "G_1") (pintype "bidirectional"))
    )
    (net (code "22") (name "LM_A") (class "Default")
      (node (ref "U$1") (pin "PB9") (pinfunction "PB9_PB9") (pintype "bidirectional"))
      (node (ref "U1") (pin "2") (pinfunction "INT1_2") (pintype "bidirectional"))
      (node (ref "U1") (pin "4") (pinfunction "INT3_4") (pintype "bidirectional"))
    )
    (net (code "23") (name "LM_B") (class "Default")
      (node (ref "U$1") (pin "PB8") (pinfunction "PB8_PB8") (pintype "bidirectional"))
      (node (ref "U1") (pin "3") (pinfunction "INT2_3") (pintype "bidirectional"))
      (node (ref "U1") (pin "5") (pinfunction "INT4_5") (pintype "bidirectional"))
    )
    (net (code "24") (name "L_CHA") (class "Default")
      (node (ref "U$1") (pin "PC14") (pinfunction "PC14_PC14") (pintype "bidirectional"))
      (node (ref "U$35") (pin "L_CHA") (pinfunction "L_CHA_L_CHA") (pintype "bidirectional"))
    )
    (net (code "25") (name "L_CHB") (class "Default")
      (node (ref "U$1") (pin "PC3") (pinfunction "PC3_PC3") (pintype "bidirectional"))
      (node (ref "U$35") (pin "L_CHB") (pinfunction "L_CHB_L_CHB") (pintype "bidirectional"))
    )
    (net (code "26") (name "Net-(C6-Pad2)") (class "Default")
      (node (ref "C6") (pin "2") (pinfunction "2_2") (pintype "passive"))
      (node (ref "U$1") (pin "VCAP_2") (pinfunction "VCAP_2_VCAP_2") (pintype "bidirectional"))
    )
    (net (code "27") (name "Net-(C9-Pad1)") (class "Default")
      (node (ref "C9") (pin "1") (pinfunction "1_1") (pintype "passive"))
      (node (ref "U$1") (pin "VCAP_1") (pinfunction "VCAP_1_VCAP_1") (pintype "bidirectional"))
    )
    (net (code "28") (name "Net-(C11-Pad1)") (class "Default")
      (node (ref "C11") (pin "1") (pinfunction "1_1") (pintype "passive"))
      (node (ref "U$4") (pin "NR/FB") (pinfunction "NR/FB_NR/FB") (pintype "bidirectional"))
    )
    (net (code "29") (name "Net-(D1-C)") (class "Default")
      (node (ref "D1") (pin "3") (pinfunction "C_3") (pintype "passive"))
      (node (ref "L2") (pin "1") (pinfunction "1_1") (pintype "passive"))
      (node (ref "U$3") (pin "2") (pinfunction "VOUT_2") (pintype "bidirectional"))
    )
    (net (code "30") (name "Net-(LED1-PadC)") (class "Default")
      (node (ref "LED1") (pin "C") (pinfunction "C_C") (pintype "passive"))
      (node (ref "R24") (pin "2") (pinfunction "2_2") (pintype "passive"))
    )
    (net (code "31") (name "Net-(LED2-PadC)") (class "Default")
      (node (ref "LED2") (pin "C") (pinfunction "C_C") (pintype "passive"))
      (node (ref "R25") (pin "2") (pinfunction "2_2") (pintype "passive"))
    )
    (net (code "32") (name "Net-(LED3-PadC)") (class "Default")
      (node (ref "LED3") (pin "C") (pinfunction "C_C") (pintype "passive"))
      (node (ref "R26") (pin "2") (pinfunction "2_2") (pintype "passive"))
    )
    (net (code "33") (name "Net-(LED4-PadC)") (class "Default")
      (node (ref "LED4") (pin "C") (pinfunction "C_C") (pintype "passive"))
      (node (ref "R27") (pin "2") (pinfunction "2_2") (pintype "passive"))
    )
    (net (code "34") (name "Net-(LED5-PadC)") (class "Default")
      (node (ref "LED5") (pin "C") (pinfunction "C_C") (pintype "passive"))
      (node (ref "R28") (pin "2") (pinfunction "2_2") (pintype "passive"))
    )
    (net (code "35") (name "Net-(LED6-PadC)") (class "Default")
      (node (ref "LED6") (pin "C") (pinfunction "C_C") (pintype "passive"))
      (node (ref "R29") (pin "2") (pinfunction "2_2") (pintype "passive"))
    )
    (net (code "36") (name "Net-(LED7-PadC)") (class "Default")
      (node (ref "LED7") (pin "C") (pinfunction "C_C") (pintype "passive"))
      (node (ref "R22") (pin "2") (pinfunction "2_2") (pintype "passive"))
    )
    (net (code "37") (name "Net-(LED8-PadC)") (class "Default")
      (node (ref "LED8") (pin "C") (pinfunction "C_C") (pintype "passive"))
      (node (ref "R23") (pin "2") (pinfunction "2_2") (pintype "passive"))
    )
    (net (code "38") (name "Net-(R1-Pad2)") (class "Default")
      (node (ref "R1") (pin "2") (pinfunction "2_2") (pintype "passive"))
      (node (ref "U$5") (pin "-") (pinfunction "-_-") (pintype "bidirectional"))
    )
    (net (code "39") (name "Net-(R2-Pad2)") (class "Default")
      (node (ref "R2") (pin "2") (pinfunction "2_2") (pintype "passive"))
      (node (ref "U$6") (pin "-") (pinfunction "-_-") (pintype "bidirectional"))
    )
    (net (code "40") (name "Net-(R3-Pad2)") (class "Default")
      (node (ref "R3") (pin "2") (pinfunction "2_2") (pintype "passive"))
      (node (ref "U$7") (pin "-") (pinfunction "-_-") (pintype "bidirectional"))
    )
    (net (code "41") (name "Net-(R4-Pad2)") (class "Default")
      (node (ref "R4") (pin "2") (pinfunction "2_2") (pintype "passive"))
      (node (ref "U$8") (pin "-") (pinfunction "-_-") (pintype "bidirectional"))
    )
    (net (code "42") (name "Net-(R5-Pad2)") (class "Default")
      (node (ref "R5") (pin "2") (pinfunction "2_2") (pintype "passive"))
      (node (ref "U$9") (pin "-") (pinfunction "-_-") (pintype "bidirectional"))
    )
    (net (code "43") (name "Net-(R6-Pad2)") (class "Default")
      (node (ref "R6") (pin "2") (pinfunction "2_2") (pintype "passive"))
      (node (ref "U$10") (pin "-") (pinfunction "-_-") (pintype "bidirectional"))
    )
    (net (code "44") (name "Net-(R7-Pad2)") (class "Default")
      (node (ref "R7") (pin "2") (pinfunction "2_2") (pintype "passive"))
      (node (ref "U$11") (pin "-") (pinfunction "-_-") (pintype "bidirectional"))
    )
    (net (code "45") (name "Net-(U$12-D)") (class "Default")
      (node (ref "R1") (pin "1") (pinfunction "1_1") (pintype "passive"))
      (node (ref "U$12") (pin "3") (pinfunction "D_3") (pintype "bidirectional"))
    )
    (net (code "46") (name "Net-(U$13-D)") (class "Default")
      (node (ref "R2") (pin "1") (pinfunction "1_1") (pintype "passive"))
      (node (ref "U$13") (pin "3") (pinfunction "D_3") (pintype "bidirectional"))
    )
    (net (code "47") (name "Net-(U$14-D)") (class "Default")
      (node (ref "R3") (pin "1") (pinfunction "1_1") (pintype "passive"))
      (node (ref "U$14") (pin "3") (pinfunction "D_3") (pintype "bidirectional"))
    )
    (net (code "48") (name "Net-(U$15-D)") (class "Default")
      (node (ref "R4") (pin "1") (pinfunction "1_1") (pintype "passive"))
      (node (ref "U$15") (pin "3") (pinfunction "D_3") (pintype "bidirectional"))
    )
    (net (code "49") (name "Net-(U$16-D)") (class "Default")
      (node (ref "R5") (pin "1") (pinfunction "1_1") (pintype "passive"))
      (node (ref "U$16") (pin "3") (pinfunction "D_3") (pintype "bidirectional"))
    )
    (net (code "50") (name "Net-(U$17-D)") (class "Default")
      (node (ref "R6") (pin "1") (pinfunction "1_1") (pintype "passive"))
      (node (ref "U$17") (pin "3") (pinfunction "D_3") (pintype "bidirectional"))
    )
    (net (code "51") (name "Net-(U$18-D)") (class "Default")
      (node (ref "R7") (pin "1") (pinfunction "1_1") (pintype "passive"))
      (node (ref "U$18") (pin "3") (pinfunction "D_3") (pintype "bidirectional"))
    )
    (net (code "52") (name "Net-(U$26-D)") (class "Default")
      (node (ref "R24") (pin "1") (pinfunction "1_1") (pintype "passive"))
      (node (ref "U$26") (pin "3") (pinfunction "D_3") (pintype "bidirectional"))
    )
    (net (code "53") (name "Net-(U$27-D)") (class "Default")
      (node (ref "R25") (pin "1") (pinfunction "1_1") (pintype "passive"))
      (node (ref "U$27") (pin "3") (pinfunction "D_3") (pintype "bidirectional"))
    )
    (net (code "54") (name "Net-(U$28-D)") (class "Default")
      (node (ref "R26") (pin "1") (pinfunction "1_1") (pintype "passive"))
      (node (ref "U$28") (pin "3") (pinfunction "D_3") (pintype "bidirectional"))
    )
    (net (code "55") (name "Net-(U$29-D)") (class "Default")
      (node (ref "R27") (pin "1") (pinfunction "1_1") (pintype "passive"))
      (node (ref "U$29") (pin "3") (pinfunction "D_3") (pintype "bidirectional"))
    )
    (net (code "56") (name "Net-(U$30-D)") (class "Default")
      (node (ref "R28") (pin "1") (pinfunction "1_1") (pintype "passive"))
      (node (ref "U$30") (pin "3") (pinfunction "D_3") (pintype "bidirectional"))
    )
    (net (code "57") (name "Net-(U$31-D)") (class "Default")
      (node (ref "R29") (pin "1") (pinfunction "1_1") (pintype "passive"))
      (node (ref "U$31") (pin "3") (pinfunction "D_3") (pintype "bidirectional"))
    )
    (net (code "58") (name "Net-(U$33-Pad-)") (class "Default")
      (node (ref "U$33") (pin "-") (pinfunction "-_-") (pintype "bidirectional"))
      (node (ref "U$34") (pin "+") (pinfunction "+_+") (pintype "bidirectional"))
    )
    (net (code "59") (name "PA3") (class "Default")
      (node (ref "J7") (pin "8") (pinfunction "8_8") (pintype "passive"))
      (node (ref "U$1") (pin "PA3") (pinfunction "PA3_PA3") (pintype "bidirectional"))
    )
    (net (code "60") (name "PA4") (class "Default")
      (node (ref "J7") (pin "7") (pinfunction "7_7") (pintype "passive"))
      (node (ref "U$1") (pin "PA4") (pinfunction "PA4_PA4") (pintype "bidirectional"))
    )
    (net (code "61") (name "PA5") (class "Default")
      (node (ref "J7") (pin "6") (pinfunction "6_6") (pintype "passive"))
      (node (ref "U$1") (pin "PA5") (pinfunction "PA5_PA5") (pintype "bidirectional"))
    )
    (net (code "62") (name "PA6") (class "Default")
      (node (ref "J7") (pin "5") (pinfunction "5_5") (pintype "passive"))
      (node (ref "U$1") (pin "PA6") (pinfunction "PA6_PA6") (pintype "bidirectional"))
    )
    (net (code "63") (name "PA7") (class "Default")
      (node (ref "J7") (pin "4") (pinfunction "4_4") (pintype "passive"))
      (node (ref "U$1") (pin "PA7") (pinfunction "PA7_PA7") (pintype "bidirectional"))
    )
    (net (code "64") (name "PA15") (class "Default")
      (node (ref "J5") (pin "8") (pinfunction "8_8") (pintype "passive"))
      (node (ref "U$1") (pin "PA15") (pinfunction "PA15_PA15") (pintype "bidirectional"))
    )
    (net (code "65") (name "PB1") (class "Default")
      (node (ref "J7") (pin "3") (pinfunction "3_3") (pintype "passive"))
      (node (ref "U$1") (pin "PB1") (pinfunction "PB1_PB1") (pintype "bidirectional"))
    )
    (net (code "66") (name "PB3") (class "Default")
      (node (ref "J5") (pin "3") (pinfunction "3_3") (pintype "passive"))
      (node (ref "U$1") (pin "PB3") (pinfunction "PB3_PB3") (pintype "bidirectional"))
    )
    (net (code "67") (name "PB4") (class "Default")
      (node (ref "J5") (pin "2") (pinfunction "2_2") (pintype "passive"))
      (node (ref "U$1") (pin "PB4") (pinfunction "PB4_PB4") (pintype "bidirectional"))
    )
    (net (code "68") (name "PB10") (class "Default")
      (node (ref "J7") (pin "2") (pinfunction "2_2") (pintype "passive"))
      (node (ref "U$1") (pin "PB10") (pinfunction "PB10_PB10") (pintype "bidirectional"))
    )
    (net (code "69") (name "PB13") (class "Default")
      (node (ref "J6") (pin "3") (pinfunction "3_3") (pintype "passive"))
      (node (ref "U$1") (pin "PB13") (pinfunction "PB13_PB13") (pintype "bidirectional"))
    )
    (net (code "70") (name "PB15") (class "Default")
      (node (ref "J6") (pin "2") (pinfunction "2_2") (pintype "passive"))
      (node (ref "U$1") (pin "PB15") (pinfunction "PB15_PB15") (pintype "bidirectional"))
    )
    (net (code "71") (name "PC7") (class "Default")
      (node (ref "J6") (pin "1") (pinfunction "1_1") (pintype "passive"))
      (node (ref "U$1") (pin "PC7") (pinfunction "PC7_PC7") (pintype "bidirectional"))
    )
    (net (code "72") (name "PC10") (class "Default")
      (node (ref "J5") (pin "7") (pinfunction "7_7") (pintype "passive"))
      (node (ref "U$1") (pin "PC10") (pinfunction "PC10_PC10") (pintype "bidirectional"))
    )
    (net (code "73") (name "PC11") (class "Default")
      (node (ref "J5") (pin "6") (pinfunction "6_6") (pintype "passive"))
      (node (ref "U$1") (pin "PC11") (pinfunction "PC11_PC11") (pintype "bidirectional"))
    )
    (net (code "74") (name "PC12") (class "Default")
      (node (ref "J5") (pin "5") (pinfunction "5_5") (pintype "passive"))
      (node (ref "U$1") (pin "PC12") (pinfunction "PC12_PC12") (pintype "bidirectional"))
    )
    (net (code "75") (name "PD2") (class "Default")
      (node (ref "J5") (pin "4") (pinfunction "4_4") (pintype "passive"))
      (node (ref "U$1") (pin "PD2") (pinfunction "PD2_PD2") (pintype "bidirectional"))
    )
    (net (code "76") (name "R1") (class "Default")
      (node (ref "U$35") (pin "R_MOTOR_A") (pinfunction "R_MOTOR_A_R_MOTOR_A") (pintype "bidirectional"))
      (node (ref "U2") (pin "10") (pinfunction "OUT1_10") (pintype "bidirectional"))
      (node (ref "U2") (pin "8") (pinfunction "OUT3_8") (pintype "bidirectional"))
    )
    (net (code "77") (name "R2") (class "Default")
      (node (ref "U$35") (pin "R_MOTOR_B") (pinfunction "R_MOTOR_B_R_MOTOR_B") (pintype "bidirectional"))
      (node (ref "U2") (pin "7") (pinfunction "OUT4_7") (pintype "bidirectional"))
      (node (ref "U2") (pin "9") (pinfunction "OUT2_9") (pintype "bidirectional"))
    )
    (net (code "78") (name "RESET") (class "Default")
      (node (ref "R36") (pin "1") (pinfunction "1_1") (pintype "passive"))
      (node (ref "S1") (pin "3") (pinfunction "2_3") (pintype "passive"))
      (node (ref "U$1") (pin "NRST") (pinfunction "NRST_NRST") (pintype "bidirectional"))
    )
    (net (code "79") (name "RM_A") (class "Default")
      (node (ref "U$1") (pin "PB7") (pinfunction "PB7_PB7") (pintype "bidirectional"))
      (node (ref "U2") (pin "2") (pinfunction "INT1_2") (pintype "bidirectional"))
      (node (ref "U2") (pin "4") (pinfunction "INT3_4") (pintype "bidirectional"))
    )
    (net (code "80") (name "RM_B") (class "Default")
      (node (ref "U$1") (pin "PB6") (pinfunction "PB6_PB6") (pintype "bidirectional"))
      (node (ref "U2") (pin "3") (pinfunction "INT2_3") (pintype "bidirectional"))
      (node (ref "U2") (pin "5") (pinfunction "INT4_5") (pintype "bidirectional"))
    )
    (net (code "81") (name "RX") (class "Default")
      (node (ref "U$1") (pin "PA10") (pinfunction "PA10_PA10") (pintype "bidirectional"))
      (node (ref "U$2") (pin "PIN7") (pinfunction "PIN7_PIN7") (pintype "bidirectional"))
    )
    (net (code "82") (name "R_CHA") (class "Default")
      (node (ref "U$1") (pin "PA0_WKUP") (pinfunction "PA0_AKUP_PA0_WKUP") (pintype "bidirectional"))
      (node (ref "U$35") (pin "R_CHA") (pinfunction "R_CHA_R_CHA") (pintype "bidirectional"))
    )
    (net (code "83") (name "R_CHB") (class "Default")
      (node (ref "U$1") (pin "PA1") (pinfunction "PA1_PA1") (pintype "bidirectional"))
      (node (ref "U$35") (pin "R_CHB") (pinfunction "R_CHB_R_CHB") (pintype "bidirectional"))
    )
    (net (code "84") (name "S1") (class "Default")
      (node (ref "R8") (pin "2") (pinfunction "2_2") (pintype "passive"))
      (node (ref "U$1") (pin "PA2") (pinfunction "PA2_PA2") (pintype "bidirectional"))
      (node (ref "U$19") (pin "E") (pinfunction "E_E") (pintype "bidirectional"))
    )
    (net (code "85") (name "S2") (class "Default")
      (node (ref "R9") (pin "2") (pinfunction "2_2") (pintype "passive"))
      (node (ref "U$1") (pin "PB0") (pinfunction "PB0_PB0") (pintype "bidirectional"))
      (node (ref "U$20") (pin "E") (pinfunction "E_E") (pintype "bidirectional"))
    )
    (net (code "86") (name "S3") (class "Default")
      (node (ref "R10") (pin "2") (pinfunction "2_2") (pintype "passive"))
      (node (ref "U$1") (pin "PC0") (pinfunction "PC0_PC0") (pintype "bidirectional"))
      (node (ref "U$21") (pin "E") (pinfunction "E_E") (pintype "bidirectional"))
    )
    (net (code "87") (name "S4") (class "Default")
      (node (ref "R11") (pin "2") (pinfunction "2_2") (pintype "passive"))
      (node (ref "U$1") (pin "PC1") (pinfunction "PC1_PC1") (pintype "bidirectional"))
      (node (ref "U$22") (pin "E") (pinfunction "E_E") (pintype "bidirectional"))
    )
    (net (code "88") (name "S5") (class "Default")
      (node (ref "R12") (pin "2") (pinfunction "2_2") (pintype "passive"))
      (node (ref "U$1") (pin "PC2") (pinfunction "PC2_PC2") (pintype "bidirectional"))
      (node (ref "U$23") (pin "E") (pinfunction "E_E") (pintype "bidirectional"))
    )
    (net (code "89") (name "S6") (class "Default")
      (node (ref "R13") (pin "2") (pinfunction "2_2") (pintype "passive"))
      (node (ref "U$1") (pin "PC4") (pinfunction "PC4_PC4") (pintype "bidirectional"))
      (node (ref "U$24") (pin "E") (pinfunction "E_E") (pintype "bidirectional"))
    )
    (net (code "90") (name "S7") (class "Default")
      (node (ref "R14") (pin "2") (pinfunction "2_2") (pintype "passive"))
      (node (ref "U$1") (pin "PC5") (pinfunction "PC5_PC5") (pintype "bidirectional"))
      (node (ref "U$25") (pin "E") (pinfunction "E_E") (pintype "bidirectional"))
    )
    (net (code "91") (name "TX") (class "Default")
      (node (ref "U$1") (pin "PA9") (pinfunction "PA9_PA9") (pintype "bidirectional"))
      (node (ref "U$2") (pin "PIN8") (pinfunction "PIN8_PIN8") (pintype "bidirectional"))
    )
    (net (code "92") (name "VBAT") (class "Default")
      (node (ref "U$32") (pin "PIN1") (pinfunction "PIN1_PIN1") (pintype "bidirectional"))
      (node (ref "U$33") (pin "+") (pinfunction "+_+") (pintype "bidirectional"))
    )
    (net (code "93") (name "VIN") (class "Default")
      (node (ref "C12") (pin "+") (pinfunction "+_+") (pintype "passive"))
      (node (ref "C14") (pin "1") (pinfunction "1_1") (pintype "passive"))
      (node (ref "C16") (pin "1") (pinfunction "1_1") (pintype "passive"))
      (node (ref "U$3") (pin "1") (pinfunction "VIN_1") (pintype "bidirectional"))
      (node (ref "U$32") (pin "PIN2") (pinfunction "PIN2_PIN2") (pintype "bidirectional"))
      (node (ref "U1") (pin "1") (pinfunction "VCC_1") (pintype "bidirectional"))
      (node (ref "U2") (pin "1") (pinfunction "VCC_1") (pintype "bidirectional"))
    )
    (net (code "94") (name "unconnected-(D1-A1-Pad1)") (class "Default")
      (node (ref "D1") (pin "1") (pinfunction "A1_1") (pintype "passive"))
    )
    (net (code "95") (name "unconnected-(U$32-PadPIN3)") (class "Default")
      (node (ref "U$32") (pin "PIN3") (pinfunction "PIN3_PIN3") (pintype "bidirectional"))
    )
  )
)
